# 0_CONNECTOR.net
KiCad netlist of a schematic drawn in Altium Designer
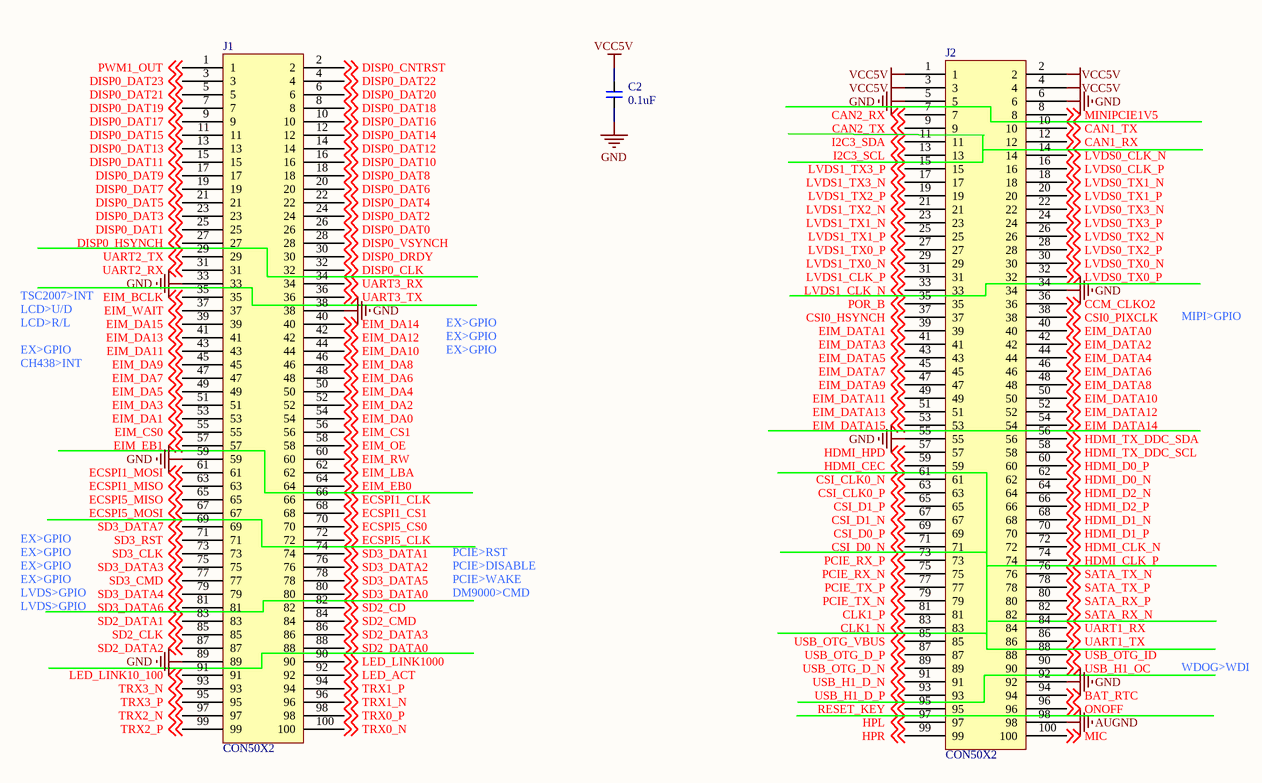
[diagram p0: 0.CONNECTOR.SchDoc]

(export (version "E")
  (design (tool "Eeschema 10.0.6"))
  (components
    (comp (ref "C2")
      (value "0.1uF")
      (footprint "0603C")
      (description "电容")
      (libsource (lib "LDT-SCH") (part "电容"))
    )
    (comp (ref "J1")
      (value "CON50X2")
      (footprint "IDC50X2-1.27MM_SMT")
      (description "ASTRON B2B Connector")
      (libsource (lib "LDT-SCH") (part "CON50X2"))
    )
    (comp (ref "J2")
      (value "CON50X2")
      (footprint "IDC50X2-1.27MM_SMT")
      (description "ASTRON B2B Connector")
      (libsource (lib "LDT-SCH") (part "CON50X2"))
    )
  )
  (nets
    (net (code "1") (name "AUGND") (class "Default")
      (node (ref "J2") (pin "98") (pinfunction "98_98") (pintype "passive"))
    )
    (net (code "2") (name "BAT_RTC") (class "Default")
      (node (ref "J2") (pin "94") (pinfunction "94_94") (pintype "passive"))
    )
    (net (code "3") (name "CAN1_RX") (class "Default")
      (node (ref "J2") (pin "12") (pinfunction "12_12") (pintype "passive"))
    )
    (net (code "4") (name "CAN1_TX") (class "Default")
      (node (ref "J2") (pin "10") (pinfunction "10_10") (pintype "passive"))
    )
    (net (code "5") (name "CAN2_RX") (class "Default")
      (node (ref "J2") (pin "7") (pinfunction "7_7") (pintype "passive"))
    )
    (net (code "6") (name "CAN2_TX") (class "Default")
      (node (ref "J2") (pin "9") (pinfunction "9_9") (pintype "passive"))
    )
    (net (code "7") (name "CCM_CLKO2") (class "Default")
      (node (ref "J2") (pin "36") (pinfunction "36_36") (pintype "passive"))
    )
    (net (code "8") (name "CLK1_N") (class "Default")
      (node (ref "J2") (pin "83") (pinfunction "83_83") (pintype "passive"))
    )
    (net (code "9") (name "CLK1_P") (class "Default")
      (node (ref "J2") (pin "81") (pinfunction "81_81") (pintype "passive"))
    )
    (net (code "10") (name "CSI0_HSYNCH") (class "Default")
      (node (ref "J2") (pin "37") (pinfunction "37_37") (pintype "passive"))
    )
    (net (code "11") (name "CSI0_PIXCLK") (class "Default")
      (node (ref "J2") (pin "38") (pinfunction "38_38") (pintype "passive"))
    )
    (net (code "12") (name "CSI_CLK0_N") (class "Default")
      (node (ref "J2") (pin "61") (pinfunction "61_61") (pintype "passive"))
    )
    (net (code "13") (name "CSI_CLK0_P") (class "Default")
      (node (ref "J2") (pin "63") (pinfunction "63_63") (pintype "passive"))
    )
    (net (code "14") (name "CSI_D0_N") (class "Default")
      (node (ref "J2") (pin "71") (pinfunction "71_71") (pintype "passive"))
    )
    (net (code "15") (name "CSI_D0_P") (class "Default")
      (node (ref "J2") (pin "69") (pinfunction "69_69") (pintype "passive"))
    )
    (net (code "16") (name "CSI_D1_N") (class "Default")
      (node (ref "J2") (pin "67") (pinfunction "67_67") (pintype "passive"))
    )
    (net (code "17") (name "CSI_D1_P") (class "Default")
      (node (ref "J2") (pin "65") (pinfunction "65_65") (pintype "passive"))
    )
    (net (code "18") (name "DISP0_CLK") (class "Default")
      (node (ref "J1") (pin "32") (pinfunction "32_32") (pintype "passive"))
    )
    (net (code "19") (name "DISP0_CNTRST") (class "Default")
      (node (ref "J1") (pin "2") (pinfunction "2_2") (pintype "passive"))
    )
    (net (code "20") (name "DISP0_DAT0") (class "Default")
      (node (ref "J1") (pin "26") (pinfunction "26_26") (pintype "passive"))
    )
    (net (code "21") (name "DISP0_DAT1") (class "Default")
      (node (ref "J1") (pin "25") (pinfunction "25_25") (pintype "passive"))
    )
    (net (code "22") (name "DISP0_DAT2") (class "Default")
      (node (ref "J1") (pin "24") (pinfunction "24_24") (pintype "passive"))
    )
    (net (code "23") (name "DISP0_DAT3") (class "Default")
      (node (ref "J1") (pin "23") (pinfunction "23_23") (pintype "passive"))
    )
    (net (code "24") (name "DISP0_DAT4") (class "Default")
      (node (ref "J1") (pin "22") (pinfunction "22_22") (pintype "passive"))
    )
    (net (code "25") (name "DISP0_DAT5") (class "Default")
      (node (ref "J1") (pin "21") (pinfunction "21_21") (pintype "passive"))
    )
    (net (code "26") (name "DISP0_DAT6") (class "Default")
      (node (ref "J1") (pin "20") (pinfunction "20_20") (pintype "passive"))
    )
    (net (code "27") (name "DISP0_DAT7") (class "Default")
      (node (ref "J1") (pin "19") (pinfunction "19_19") (pintype "passive"))
    )
    (net (code "28") (name "DISP0_DAT8") (class "Default")
      (node (ref "J1") (pin "18") (pinfunction "18_18") (pintype "passive"))
    )
    (net (code "29") (name "DISP0_DAT9") (class "Default")
      (node (ref "J1") (pin "17") (pinfunction "17_17") (pintype "passive"))
    )
    (net (code "30") (name "DISP0_DAT10") (class "Default")
      (node (ref "J1") (pin "16") (pinfunction "16_16") (pintype "passive"))
    )
    (net (code "31") (name "DISP0_DAT11") (class "Default")
      (node (ref "J1") (pin "15") (pinfunction "15_15") (pintype "passive"))
    )
    (net (code "32") (name "DISP0_DAT12") (class "Default")
      (node (ref "J1") (pin "14") (pinfunction "14_14") (pintype "passive"))
    )
    (net (code "33") (name "DISP0_DAT13") (class "Default")
      (node (ref "J1") (pin "13") (pinfunction "13_13") (pintype "passive"))
    )
    (net (code "34") (name "DISP0_DAT14") (class "Default")
      (node (ref "J1") (pin "12") (pinfunction "12_12") (pintype "passive"))
    )
    (net (code "35") (name "DISP0_DAT15") (class "Default")
      (node (ref "J1") (pin "11") (pinfunction "11_11") (pintype "passive"))
    )
    (net (code "36") (name "DISP0_DAT16") (class "Default")
      (node (ref "J1") (pin "10") (pinfunction "10_10") (pintype "passive"))
    )
    (net (code "37") (name "DISP0_DAT17") (class "Default")
      (node (ref "J1") (pin "9") (pinfunction "9_9") (pintype "passive"))
    )
    (net (code "38") (name "DISP0_DAT18") (class "Default")
      (node (ref "J1") (pin "8") (pinfunction "8_8") (pintype "passive"))
    )
    (net (code "39") (name "DISP0_DAT19") (class "Default")
      (node (ref "J1") (pin "7") (pinfunction "7_7") (pintype "passive"))
    )
    (net (code "40") (name "DISP0_DAT20") (class "Default")
      (node (ref "J1") (pin "6") (pinfunction "6_6") (pintype "passive"))
    )
    (net (code "41") (name "DISP0_DAT21") (class "Default")
      (node (ref "J1") (pin "5") (pinfunction "5_5") (pintype "passive"))
    )
    (net (code "42") (name "DISP0_DAT22") (class "Default")
      (node (ref "J1") (pin "4") (pinfunction "4_4") (pintype "passive"))
    )
    (net (code "43") (name "DISP0_DAT23") (class "Default")
      (node (ref "J1") (pin "3") (pinfunction "3_3") (pintype "passive"))
    )
    (net (code "44") (name "DISP0_DRDY") (class "Default")
      (node (ref "J1") (pin "30") (pinfunction "30_30") (pintype "passive"))
    )
    (net (code "45") (name "DISP0_HSYNCH") (class "Default")
      (node (ref "J1") (pin "27") (pinfunction "27_27") (pintype "passive"))
    )
    (net (code "46") (name "DISP0_VSYNCH") (class "Default")
      (node (ref "J1") (pin "28") (pinfunction "28_28") (pintype "passive"))
    )
    (net (code "47") (name "ECSPI1_CLK") (class "Default")
      (node (ref "J1") (pin "66") (pinfunction "66_66") (pintype "passive"))
    )
    (net (code "48") (name "ECSPI1_CS1") (class "Default")
      (node (ref "J1") (pin "68") (pinfunction "68_68") (pintype "passive"))
    )
    (net (code "49") (name "ECSPI1_MISO") (class "Default")
      (node (ref "J1") (pin "63") (pinfunction "63_63") (pintype "passive"))
    )
    (net (code "50") (name "ECSPI1_MOSI") (class "Default")
      (node (ref "J1") (pin "61") (pinfunction "61_61") (pintype "passive"))
    )
    (net (code "51") (name "ECSPI5_CLK") (class "Default")
      (node (ref "J1") (pin "72") (pinfunction "72_72") (pintype "passive"))
    )
    (net (code "52") (name "ECSPI5_CS0") (class "Default")
      (node (ref "J1") (pin "70") (pinfunction "70_70") (pintype "passive"))
    )
    (net (code "53") (name "ECSPI5_MISO") (class "Default")
      (node (ref "J1") (pin "65") (pinfunction "65_65") (pintype "passive"))
    )
    (net (code "54") (name "ECSPI5_MOSI") (class "Default")
      (node (ref "J1") (pin "67") (pinfunction "67_67") (pintype "passive"))
    )
    (net (code "55") (name "EIM_BCLK") (class "Default")
      (node (ref "J1") (pin "35") (pinfunction "35_35") (pintype "passive"))
    )
    (net (code "56") (name "EIM_CS0") (class "Default")
      (node (ref "J1") (pin "55") (pinfunction "55_55") (pintype "passive"))
    )
    (net (code "57") (name "EIM_CS1") (class "Default")
      (node (ref "J1") (pin "56") (pinfunction "56_56") (pintype "passive"))
    )
    (net (code "58") (name "EIM_DA0") (class "Default")
      (node (ref "J1") (pin "54") (pinfunction "54_54") (pintype "passive"))
    )
    (net (code "59") (name "EIM_DA1") (class "Default")
      (node (ref "J1") (pin "53") (pinfunction "53_53") (pintype "passive"))
    )
    (net (code "60") (name "EIM_DA2") (class "Default")
      (node (ref "J1") (pin "52") (pinfunction "52_52") (pintype "passive"))
    )
    (net (code "61") (name "EIM_DA3") (class "Default")
      (node (ref "J1") (pin "51") (pinfunction "51_51") (pintype "passive"))
    )
    (net (code "62") (name "EIM_DA4") (class "Default")
      (node (ref "J1") (pin "50") (pinfunction "50_50") (pintype "passive"))
    )
    (net (code "63") (name "EIM_DA5") (class "Default")
      (node (ref "J1") (pin "49") (pinfunction "49_49") (pintype "passive"))
    )
    (net (code "64") (name "EIM_DA6") (class "Default")
      (node (ref "J1") (pin "48") (pinfunction "48_48") (pintype "passive"))
    )
    (net (code "65") (name "EIM_DA7") (class "Default")
      (node (ref "J1") (pin "47") (pinfunction "47_47") (pintype "passive"))
    )
    (net (code "66") (name "EIM_DA8") (class "Default")
      (node (ref "J1") (pin "46") (pinfunction "46_46") (pintype "passive"))
    )
    (net (code "67") (name "EIM_DA9") (class "Default")
      (node (ref "J1") (pin "45") (pinfunction "45_45") (pintype "passive"))
    )
    (net (code "68") (name "EIM_DA10") (class "Default")
      (node (ref "J1") (pin "44") (pinfunction "44_44") (pintype "passive"))
    )
    (net (code "69") (name "EIM_DA11") (class "Default")
      (node (ref "J1") (pin "43") (pinfunction "43_43") (pintype "passive"))
    )
    (net (code "70") (name "EIM_DA12") (class "Default")
      (node (ref "J1") (pin "42") (pinfunction "42_42") (pintype "passive"))
    )
    (net (code "71") (name "EIM_DA13") (class "Default")
      (node (ref "J1") (pin "41") (pinfunction "41_41") (pintype "passive"))
    )
    (net (code "72") (name "EIM_DA14") (class "Default")
      (node (ref "J1") (pin "40") (pinfunction "40_40") (pintype "passive"))
    )
    (net (code "73") (name "EIM_DA15") (class "Default")
      (node (ref "J1") (pin "39") (pinfunction "39_39") (pintype "passive"))
    )
    (net (code "74") (name "EIM_DATA0") (class "Default")
      (node (ref "J2") (pin "40") (pinfunction "40_40") (pintype "passive"))
    )
    (net (code "75") (name "EIM_DATA1") (class "Default")
      (node (ref "J2") (pin "39") (pinfunction "39_39") (pintype "passive"))
    )
    (net (code "76") (name "EIM_DATA2") (class "Default")
      (node (ref "J2") (pin "42") (pinfunction "42_42") (pintype "passive"))
    )
    (net (code "77") (name "EIM_DATA3") (class "Default")
      (node (ref "J2") (pin "41") (pinfunction "41_41") (pintype "passive"))
    )
    (net (code "78") (name "EIM_DATA4") (class "Default")
      (node (ref "J2") (pin "44") (pinfunction "44_44") (pintype "passive"))
    )
    (net (code "79") (name "EIM_DATA5") (class "Default")
      (node (ref "J2") (pin "43") (pinfunction "43_43") (pintype "passive"))
    )
    (net (code "80") (name "EIM_DATA6") (class "Default")
      (node (ref "J2") (pin "46") (pinfunction "46_46") (pintype "passive"))
    )
    (net (code "81") (name "EIM_DATA7") (class "Default")
      (node (ref "J2") (pin "45") (pinfunction "45_45") (pintype "passive"))
    )
    (net (code "82") (name "EIM_DATA8") (class "Default")
      (node (ref "J2") (pin "48") (pinfunction "48_48") (pintype "passive"))
    )
    (net (code "83") (name "EIM_DATA9") (class "Default")
      (node (ref "J2") (pin "47") (pinfunction "47_47") (pintype "passive"))
    )
    (net (code "84") (name "EIM_DATA10") (class "Default")
      (node (ref "J2") (pin "50") (pinfunction "50_50") (pintype "passive"))
    )
    (net (code "85") (name "EIM_DATA11") (class "Default")
      (node (ref "J2") (pin "49") (pinfunction "49_49") (pintype "passive"))
    )
    (net (code "86") (name "EIM_DATA12") (class "Default")
      (node (ref "J2") (pin "52") (pinfunction "52_52") (pintype "passive"))
    )
    (net (code "87") (name "EIM_DATA13") (class "Default")
      (node (ref "J2") (pin "51") (pinfunction "51_51") (pintype "passive"))
    )
    (net (code "88") (name "EIM_DATA14") (class "Default")
      (node (ref "J2") (pin "54") (pinfunction "54_54") (pintype "passive"))
    )
    (net (code "89") (name "EIM_DATA15") (class "Default")
      (node (ref "J2") (pin "53") (pinfunction "53_53") (pintype "passive"))
    )
    (net (code "90") (name "EIM_EB0") (class "Default")
      (node (ref "J1") (pin "64") (pinfunction "64_64") (pintype "passive"))
    )
    (net (code "91") (name "EIM_EB1") (class "Default")
      (node (ref "J1") (pin "57") (pinfunction "57_57") (pintype "passive"))
    )
    (net (code "92") (name "EIM_LBA") (class "Default")
      (node (ref "J1") (pin "62") (pinfunction "62_62") (pintype "passive"))
    )
    (net (code "93") (name "EIM_OE") (class "Default")
      (node (ref "J1") (pin "58") (pinfunction "58_58") (pintype "passive"))
    )
    (net (code "94") (name "EIM_RW") (class "Default")
      (node (ref "J1") (pin "60") (pinfunction "60_60") (pintype "passive"))
    )
    (net (code "95") (name "EIM_WAIT") (class "Default")
      (node (ref "J1") (pin "37") (pinfunction "37_37") (pintype "passive"))
    )
    (net (code "96") (name "GND") (class "Default")
      (node (ref "C2") (pin "2") (pintype "passive"))
      (node (ref "J1") (pin "33") (pinfunction "33_33") (pintype "passive"))
      (node (ref "J1") (pin "38") (pinfunction "38_38") (pintype "passive"))
      (node (ref "J1") (pin "59") (pinfunction "59_59") (pintype "passive"))
      (node (ref "J1") (pin "89") (pinfunction "89_89") (pintype "passive"))
      (node (ref "J2") (pin "34") (pinfunction "34_34") (pintype "passive"))
      (node (ref "J2") (pin "5") (pinfunction "5_5") (pintype "passive"))
      (node (ref "J2") (pin "55") (pinfunction "55_55") (pintype "passive"))
      (node (ref "J2") (pin "6") (pinfunction "6_6") (pintype "passive"))
      (node (ref "J2") (pin "92") (pinfunction "92_92") (pintype "passive"))
    )
    (net (code "97") (name "HDMI_CEC") (class "Default")
      (node (ref "J2") (pin "59") (pinfunction "59_59") (pintype "passive"))
    )
    (net (code "98") (name "HDMI_CLK_N") (class "Default")
      (node (ref "J2") (pin "72") (pinfunction "72_72") (pintype "passive"))
    )
    (net (code "99") (name "HDMI_CLK_P") (class "Default")
      (node (ref "J2") (pin "74") (pinfunction "74_74") (pintype "passive"))
    )
    (net (code "100") (name "HDMI_D0_N") (class "Default")
      (node (ref "J2") (pin "62") (pinfunction "62_62") (pintype "passive"))
    )
    (net (code "101") (name "HDMI_D0_P") (class "Default")
      (node (ref "J2") (pin "60") (pinfunction "60_60") (pintype "passive"))
    )
    (net (code "102") (name "HDMI_D1_N") (class "Default")
      (node (ref "J2") (pin "68") (pinfunction "68_68") (pintype "passive"))
    )
    (net (code "103") (name "HDMI_D1_P") (class "Default")
      (node (ref "J2") (pin "70") (pinfunction "70_70") (pintype "passive"))
    )
    (net (code "104") (name "HDMI_D2_N") (class "Default")
      (node (ref "J2") (pin "64") (pinfunction "64_64") (pintype "passive"))
    )
    (net (code "105") (name "HDMI_D2_P") (class "Default")
      (node (ref "J2") (pin "66") (pinfunction "66_66") (pintype "passive"))
    )
    (net (code "106") (name "HDMI_HPD") (class "Default")
      (node (ref "J2") (pin "57") (pinfunction "57_57") (pintype "passive"))
    )
    (net (code "107") (name "HDMI_TX_DDC_SCL") (class "Default")
      (node (ref "J2") (pin "58") (pinfunction "58_58") (pintype "passive"))
    )
    (net (code "108") (name "HDMI_TX_DDC_SDA") (class "Default")
      (node (ref "J2") (pin "56") (pinfunction "56_56") (pintype "passive"))
    )
    (net (code "109") (name "HPL") (class "Default")
      (node (ref "J2") (pin "97") (pinfunction "97_97") (pintype "passive"))
    )
    (net (code "110") (name "HPR") (class "Default")
      (node (ref "J2") (pin "99") (pinfunction "99_99") (pintype "passive"))
    )
    (net (code "111") (name "I2C3_SCL") (class "Default")
      (node (ref "J2") (pin "13") (pinfunction "13_13") (pintype "passive"))
    )
    (net (code "112") (name "I2C3_SDA") (class "Default")
      (node (ref "J2") (pin "11") (pinfunction "11_11") (pintype "passive"))
    )
    (net (code "113") (name "LED_ACT") (class "Default")
      (node (ref "J1") (pin "92") (pinfunction "92_92") (pintype "passive"))
    )
    (net (code "114") (name "LED_LINK10_100") (class "Default")
      (node (ref "J1") (pin "91") (pinfunction "91_91") (pintype "passive"))
    )
    (net (code "115") (name "LED_LINK1000") (class "Default")
      (node (ref "J1") (pin "90") (pinfunction "90_90") (pintype "passive"))
    )
    (net (code "116") (name "LVDS0_CLK_N") (class "Default")
      (node (ref "J2") (pin "14") (pinfunction "14_14") (pintype "passive"))
    )
    (net (code "117") (name "LVDS0_CLK_P") (class "Default")
      (node (ref "J2") (pin "16") (pinfunction "16_16") (pintype "passive"))
    )
    (net (code "118") (name "LVDS0_TX0_N") (class "Default")
      (node (ref "J2") (pin "30") (pinfunction "30_30") (pintype "passive"))
    )
    (net (code "119") (name "LVDS0_TX0_P") (class "Default")
      (node (ref "J2") (pin "32") (pinfunction "32_32") (pintype "passive"))
    )
    (net (code "120") (name "LVDS0_TX1_N") (class "Default")
      (node (ref "J2") (pin "18") (pinfunction "18_18") (pintype "passive"))
    )
    (net (code "121") (name "LVDS0_TX1_P") (class "Default")
      (node (ref "J2") (pin "20") (pinfunction "20_20") (pintype "passive"))
    )
    (net (code "122") (name "LVDS0_TX2_N") (class "Default")
      (node (ref "J2") (pin "26") (pinfunction "26_26") (pintype "passive"))
    )
    (net (code "123") (name "LVDS0_TX2_P") (class "Default")
      (node (ref "J2") (pin "28") (pinfunction "28_28") (pintype "passive"))
    )
    (net (code "124") (name "LVDS0_TX3_N") (class "Default")
      (node (ref "J2") (pin "22") (pinfunction "22_22") (pintype "passive"))
    )
    (net (code "125") (name "LVDS0_TX3_P") (class "Default")
      (node (ref "J2") (pin "24") (pinfunction "24_24") (pintype "passive"))
    )
    (net (code "126") (name "LVDS1_CLK_N") (class "Default")
      (node (ref "J2") (pin "33") (pinfunction "33_33") (pintype "passive"))
    )
    (net (code "127") (name "LVDS1_CLK_P") (class "Default")
      (node (ref "J2") (pin "31") (pinfunction "31_31") (pintype "passive"))
    )
    (net (code "128") (name "LVDS1_TX0_N") (class "Default")
      (node (ref "J2") (pin "29") (pinfunction "29_29") (pintype "passive"))
    )
    (net (code "129") (name "LVDS1_TX0_P") (class "Default")
      (node (ref "J2") (pin "27") (pinfunction "27_27") (pintype "passive"))
    )
    (net (code "130") (name "LVDS1_TX1_N") (class "Default")
      (node (ref "J2") (pin "23") (pinfunction "23_23") (pintype "passive"))
    )
    (net (code "131") (name "LVDS1_TX1_P") (class "Default")
      (node (ref "J2") (pin "25") (pinfunction "25_25") (pintype "passive"))
    )
    (net (code "132") (name "LVDS1_TX2_N") (class "Default")
      (node (ref "J2") (pin "21") (pinfunction "21_21") (pintype "passive"))
    )
    (net (code "133") (name "LVDS1_TX2_P") (class "Default")
      (node (ref "J2") (pin "19") (pinfunction "19_19") (pintype "passive"))
    )
    (net (code "134") (name "LVDS1_TX3_N") (class "Default")
      (node (ref "J2") (pin "17") (pinfunction "17_17") (pintype "passive"))
    )
    (net (code "135") (name "LVDS1_TX3_P") (class "Default")
      (node (ref "J2") (pin "15") (pinfunction "15_15") (pintype "passive"))
    )
    (net (code "136") (name "MIC") (class "Default")
      (node (ref "J2") (pin "100") (pinfunction "100_100") (pintype "passive"))
    )
    (net (code "137") (name "MINIPCIE1V5") (class "Default")
      (node (ref "J2") (pin "8") (pinfunction "8_8") (pintype "passive"))
    )
    (net (code "138") (name "ONOFF") (class "Default")
      (node (ref "J2") (pin "96") (pinfunction "96_96") (pintype "passive"))
    )
    (net (code "139") (name "PCIE_RX_N") (class "Default")
      (node (ref "J2") (pin "75") (pinfunction "75_75") (pintype "passive"))
    )
    (net (code "140") (name "PCIE_RX_P") (class "Default")
      (node (ref "J2") (pin "73") (pinfunction "73_73") (pintype "passive"))
    )
    (net (code "141") (name "PCIE_TX_N") (class "Default")
      (node (ref "J2") (pin "79") (pinfunction "79_79") (pintype "passive"))
    )
    (net (code "142") (name "PCIE_TX_P") (class "Default")
      (node (ref "J2") (pin "77") (pinfunction "77_77") (pintype "passive"))
    )
    (net (code "143") (name "POR_B") (class "Default")
      (node (ref "J2") (pin "35") (pinfunction "35_35") (pintype "passive"))
    )
    (net (code "144") (name "PWM1_OUT") (class "Default")
      (node (ref "J1") (pin "1") (pinfunction "1_1") (pintype "passive"))
    )
    (net (code "145") (name "RESET_KEY") (class "Default")
      (node (ref "J2") (pin "95") (pinfunction "95_95") (pintype "passive"))
    )
    (net (code "146") (name "SATA_RX_N") (class "Default")
      (node (ref "J2") (pin "82") (pinfunction "82_82") (pintype "passive"))
    )
    (net (code "147") (name "SATA_RX_P") (class "Default")
      (node (ref "J2") (pin "80") (pinfunction "80_80") (pintype "passive"))
    )
    (net (code "148") (name "SATA_TX_N") (class "Default")
      (node (ref "J2") (pin "76") (pinfunction "76_76") (pintype "passive"))
    )
    (net (code "149") (name "SATA_TX_P") (class "Default")
      (node (ref "J2") (pin "78") (pinfunction "78_78") (pintype "passive"))
    )
    (net (code "150") (name "SD2_CD") (class "Default")
      (node (ref "J1") (pin "82") (pinfunction "82_82") (pintype "passive"))
    )
    (net (code "151") (name "SD2_CLK") (class "Default")
      (node (ref "J1") (pin "85") (pinfunction "85_85") (pintype "passive"))
    )
    (net (code "152") (name "SD2_CMD") (class "Default")
      (node (ref "J1") (pin "84") (pinfunction "84_84") (pintype "passive"))
    )
    (net (code "153") (name "SD2_DATA0") (class "Default")
      (node (ref "J1") (pin "88") (pinfunction "88_88") (pintype "passive"))
    )
    (net (code "154") (name "SD2_DATA1") (class "Default")
      (node (ref "J1") (pin "83") (pinfunction "83_83") (pintype "passive"))
    )
    (net (code "155") (name "SD2_DATA2") (class "Default")
      (node (ref "J1") (pin "87") (pinfunction "87_87") (pintype "passive"))
    )
    (net (code "156") (name "SD2_DATA3") (class "Default")
      (node (ref "J1") (pin "86") (pinfunction "86_86") (pintype "passive"))
    )
    (net (code "157") (name "SD3_CLK") (class "Default")
      (node (ref "J1") (pin "73") (pinfunction "73_73") (pintype "passive"))
    )
    (net (code "158") (name "SD3_CMD") (class "Default")
      (node (ref "J1") (pin "77") (pinfunction "77_77") (pintype "passive"))
    )
    (net (code "159") (name "SD3_DATA0") (class "Default")
      (node (ref "J1") (pin "80") (pinfunction "80_80") (pintype "passive"))
    )
    (net (code "160") (name "SD3_DATA1") (class "Default")
      (node (ref "J1") (pin "74") (pinfunction "74_74") (pintype "passive"))
    )
    (net (code "161") (name "SD3_DATA2") (class "Default")
      (node (ref "J1") (pin "76") (pinfunction "76_76") (pintype "passive"))
    )
    (net (code "162") (name "SD3_DATA3") (class "Default")
      (node (ref "J1") (pin "75") (pinfunction "75_75") (pintype "passive"))
    )
    (net (code "163") (name "SD3_DATA4") (class "Default")
      (node (ref "J1") (pin "79") (pinfunction "79_79") (pintype "passive"))
    )
    (net (code "164") (name "SD3_DATA5") (class "Default")
      (node (ref "J1") (pin "78") (pinfunction "78_78") (pintype "passive"))
    )
    (net (code "165") (name "SD3_DATA6") (class "Default")
      (node (ref "J1") (pin "81") (pinfunction "81_81") (pintype "passive"))
    )
    (net (code "166") (name "SD3_DATA7") (class "Default")
      (node (ref "J1") (pin "69") (pinfunction "69_69") (pintype "passive"))
    )
    (net (code "167") (name "SD3_RST") (class "Default")
      (node (ref "J1") (pin "71") (pinfunction "71_71") (pintype "passive"))
    )
    (net (code "168") (name "TRX0_N") (class "Default")
      (node (ref "J1") (pin "100") (pinfunction "100_100") (pintype "passive"))
    )
    (net (code "169") (name "TRX0_P") (class "Default")
      (node (ref "J1") (pin "98") (pinfunction "98_98") (pintype "passive"))
    )
    (net (code "170") (name "TRX1_N") (class "Default")
      (node (ref "J1") (pin "96") (pinfunction "96_96") (pintype "passive"))
    )
    (net (code "171") (name "TRX1_P") (class "Default")
      (node (ref "J1") (pin "94") (pinfunction "94_94") (pintype "passive"))
    )
    (net (code "172") (name "TRX2_N") (class "Default")
      (node (ref "J1") (pin "97") (pinfunction "97_97") (pintype "passive"))
    )
    (net (code "173") (name "TRX2_P") (class "Default")
      (node (ref "J1") (pin "99") (pinfunction "99_99") (pintype "passive"))
    )
    (net (code "174") (name "TRX3_N") (class "Default")
      (node (ref "J1") (pin "93") (pinfunction "93_93") (pintype "passive"))
    )
    (net (code "175") (name "TRX3_P") (class "Default")
      (node (ref "J1") (pin "95") (pinfunction "95_95") (pintype "passive"))
    )
    (net (code "176") (name "UART1_RX") (class "Default")
      (node (ref "J2") (pin "84") (pinfunction "84_84") (pintype "passive"))
    )
    (net (code "177") (name "UART1_TX") (class "Default")
      (node (ref "J2") (pin "86") (pinfunction "86_86") (pintype "passive"))
    )
    (net (code "178") (name "UART2_RX") (class "Default")
      (node (ref "J1") (pin "31") (pinfunction "31_31") (pintype "passive"))
    )
    (net (code "179") (name "UART2_TX") (class "Default")
      (node (ref "J1") (pin "29") (pinfunction "29_29") (pintype "passive"))
    )
    (net (code "180") (name "UART3_RX") (class "Default")
      (node (ref "J1") (pin "34") (pinfunction "34_34") (pintype "passive"))
    )
    (net (code "181") (name "UART3_TX") (class "Default")
      (node (ref "J1") (pin "36") (pinfunction "36_36") (pintype "passive"))
    )
    (net (code "182") (name "USB_H1_D_N") (class "Default")
      (node (ref "J2") (pin "91") (pinfunction "91_91") (pintype "passive"))
    )
    (net (code "183") (name "USB_H1_D_P") (class "Default")
      (node (ref "J2") (pin "93") (pinfunction "93_93") (pintype "passive"))
    )
    (net (code "184") (name "USB_H1_OC") (class "Default")
      (node (ref "J2") (pin "90") (pinfunction "90_90") (pintype "passive"))
    )
    (net (code "185") (name "USB_OTG_D_N") (class "Default")
      (node (ref "J2") (pin "89") (pinfunction "89_89") (pintype "passive"))
    )
    (net (code "186") (name "USB_OTG_D_P") (class "Default")
      (node (ref "J2") (pin "87") (pinfunction "87_87") (pintype "passive"))
    )
    (net (code "187") (name "USB_OTG_ID") (class "Default")
      (node (ref "J2") (pin "88") (pinfunction "88_88") (pintype "passive"))
    )
    (net (code "188") (name "USB_OTG_VBUS") (class "Default")
      (node (ref "J2") (pin "85") (pinfunction "85_85") (pintype "passive"))
    )
    (net (code "189") (name "VCC5V") (class "Default")
      (node (ref "C2") (pin "1") (pintype "passive"))
      (node (ref "J2") (pin "1") (pinfunction "1_1") (pintype "passive"))
      (node (ref "J2") (pin "2") (pinfunction "2_2") (pintype "passive"))
      (node (ref "J2") (pin "3") (pinfunction "3_3") (pintype "passive"))
      (node (ref "J2") (pin "4") (pinfunction "4_4") (pintype "passive"))
    )
  )
)
